# POWER.net
KiCad netlist of a schematic drawn in Altium Designer
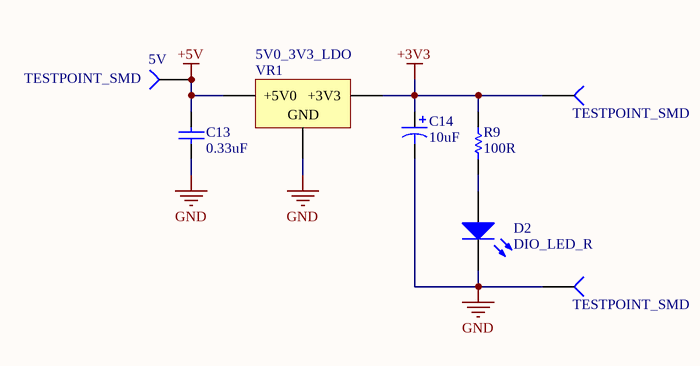
[diagram p0: POWER.SchDoc]

(export (version "E")
  (design (tool "Eeschema 10.0.6"))
  (components
    (comp (ref "3V3")
      (value "TESTPOINT_SMD")
      (footprint "TESTPOINT")
      (libsource (lib "UWRT_Schematic_Library_2019") (part "TESTPOINT_SMD"))
    )
    (comp (ref "5V")
      (value "TESTPOINT_SMD")
      (footprint "TESTPOINT")
      (libsource (lib "UWRT_Schematic_Library_2019") (part "TESTPOINT_SMD"))
    )
    (comp (ref "C13")
      (value "0.33uF")
      (footprint "CAPC0603(1608)55_N")
      (description "CAP CER 0.33UF 16V X7R 0603")
      (fields
        (field (name "MANUFACTURER") "Murata Electronics North America")
        (field (name "MPN") "GCM188R71C334KA37D")
      )
      (libsource (lib "UWRT_Schematic_Library_2019") (part "CAP_0.33uF_16V_0603"))
    )
    (comp (ref "C14")
      (value "10uF")
      (footprint "AVX-CAPC3528_V")
      (description "CAP TANT 10UF 20% 10V 1411")
      (fields (field (name "MPN") "F971A106MBAHT3") (field (name "MANUFACTURER") "AVX Corporation"))
      (libsource (lib "UWRT_Schematic_Library_2019") (part "CAP_10uF_1411_POL"))
    )
    (comp (ref "D2")
      (value "DIO_LED_R")
      (footprint "LED_0805_LINE")
      (description "LED RED DIFFUSED 0805 SMD")
      (fields (field (name "MANUFACTURER") "OSRAM") (field (name "MPN") "LS R976-NR-1"))
      (libsource (lib "UWRT_Schematic_Library_2019") (part "DIO_LED_R"))
    )
    (comp (ref "GND")
      (value "TESTPOINT_SMD")
      (footprint "TESTPOINT")
      (libsource (lib "UWRT_Schematic_Library_2019") (part "TESTPOINT_SMD"))
    )
    (comp (ref "R9")
      (value "100R")
      (footprint "RESC0603(1608)_N")
      (description "RES SMD 100 OHM 1% 1/10W 0603")
      (fields (field (name "MANUFACTURER") "Yageo") (field (name "TOLERANCE") "1%"))
      (libsource (lib "UWRT_Schematic_Library_2019") (part "RES_100R_0603"))
    )
    (comp (ref "VR1")
      (value "5V0_3V3_LDO")
      (footprint "UWRT_Footprint_Library_2019:VOLTAGE_REGULATOR")
      (description "IC REG LINEAR 3.3V 1A DPAK")
      (fields (field (name "MANUFACTURER") "ON Semiconductor") (field (name "MPN") "NCP1117DT33T5G"))
      (libsource (lib "UWRT_Schematic_Library_2019") (part "5V0_3V3_LDO"))
    )
  )
  (nets
    (net (code "1") (name "+3V3") (class "Default")
      (node (ref "3V3") (pin "1") (pinfunction "=value_1") (pintype "passive"))
      (node (ref "C14") (pin "1") (pinfunction "1_1") (pintype "passive"))
      (node (ref "R9") (pin "2") (pinfunction "2_2") (pintype "passive"))
      (node (ref "VR1") (pin "2") (pinfunction "+3V3_2") (pintype "passive"))
    )
    (net (code "2") (name "+5V") (class "Default")
      (node (ref "5V") (pin "1") (pinfunction "=value_1") (pintype "passive"))
      (node (ref "C13") (pin "2") (pinfunction "2_2") (pintype "passive"))
      (node (ref "VR1") (pin "3") (pinfunction "+5V0_3") (pintype "passive"))
    )
    (net (code "3") (name "GND") (class "Default")
      (node (ref "C13") (pin "1") (pinfunction "1_1") (pintype "passive"))
      (node (ref "C14") (pin "2") (pinfunction "2_2") (pintype "passive"))
      (node (ref "D2") (pin "2") (pinfunction "K_2") (pintype "passive"))
      (node (ref "GND") (pin "1") (pinfunction "=value_1") (pintype "passive"))
      (node (ref "VR1") (pin "1") (pinfunction "GND_1") (pintype "passive"))
    )
    (net (code "4") (name "Net-(D2-A)") (class "Default")
      (node (ref "D2") (pin "1") (pinfunction "A_1") (pintype "passive"))
      (node (ref "R9") (pin "1") (pinfunction "1_1") (pintype "passive"))
    )
  )
)
